# clock.net
KiCad netlist of a schematic drawn in EAGLE
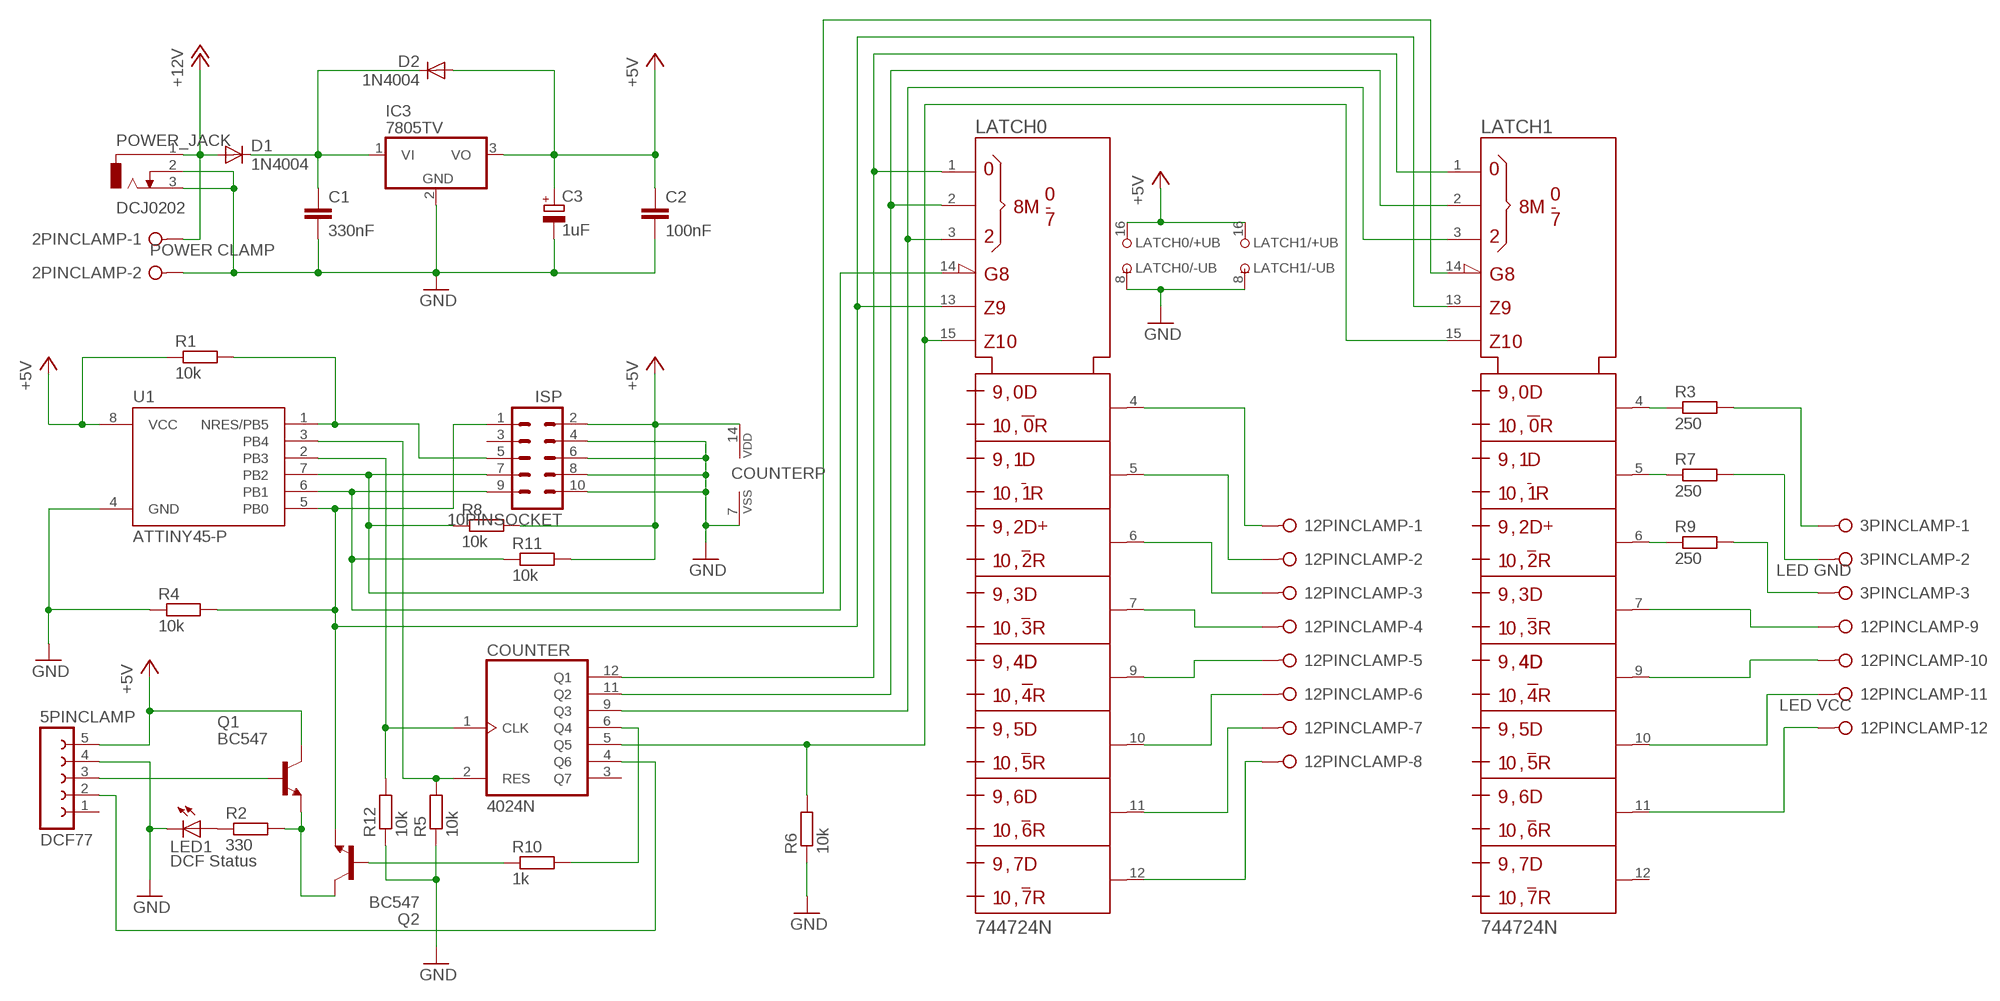
[diagram p0: schematic, sheet 1]

(export (version "E")
  (design (tool "Eeschema 10.0.6"))
  (components
    (comp (ref "2PINCLAMP")
      (value "POWER CLAMP")
      (footprint "eagle-import:W237-132")
      (libsource (lib "eagle-import") (part "W237-02P"))
    )
    (comp (ref "3PINCLAMP")
      (value "LED GND")
      (footprint "eagle-import:W237-3E")
      (libsource (lib "eagle-import") (part "W237-3E"))
    )
    (comp (ref "5PINCLAMP")
      (value "DCF77")
      (footprint "eagle-import:FE05-1")
      (libsource (lib "eagle-import") (part "FE05-1"))
    )
    (comp (ref "10PINSOCKET")
      (value "ISP")
      (footprint "eagle-import:ML10")
      (libsource (lib "eagle-import") (part "ML10"))
    )
    (comp (ref "12PINCLAMP")
      (value "LED VCC")
      (footprint "eagle-import:W237-12P")
      (libsource (lib "eagle-import") (part "W237-12P"))
    )
    (comp (ref "C1")
      (value "330nF")
      (footprint "eagle-import:C050-025X075")
      (libsource (lib "eagle-import") (part "C-EU050-025X075"))
    )
    (comp (ref "C2")
      (value "100nF")
      (footprint "eagle-import:C050-025X075")
      (libsource (lib "eagle-import") (part "C-EU050-025X075"))
    )
    (comp (ref "C3")
      (value "1uF")
      (footprint "eagle-import:E2-4")
      (libsource (lib "eagle-import") (part "CPOL-EUE2-4"))
    )
    (comp (ref "COUNTER")
      (value "4024N")
      (footprint "eagle-import:DIL14")
      (libsource (lib "eagle-import") (part "4024N"))
    )
    (comp (ref "D1")
      (value "1N4004")
      (footprint "eagle-import:DO41-10")
      (libsource (lib "eagle-import") (part "1N4004"))
    )
    (comp (ref "D2")
      (value "1N4004")
      (footprint "eagle-import:DO41-10")
      (libsource (lib "eagle-import") (part "1N4004"))
    )
    (comp (ref "IC3")
      (value "7805TV")
      (footprint "eagle-import:TO220V")
      (libsource (lib "eagle-import") (part "78TV05"))
    )
    (comp (ref "LATCH0")
      (value "744724N")
      (footprint "eagle-import:DIL16")
      (libsource (lib "eagle-import") (part "744724N"))
    )
    (comp (ref "LATCH1")
      (value "744724N")
      (footprint "eagle-import:DIL16")
      (libsource (lib "eagle-import") (part "744724N"))
    )
    (comp (ref "LED1")
      (value "DCF Status")
      (footprint "eagle-import:LED5MM")
      (libsource (lib "eagle-import") (part "LED5MM"))
    )
    (comp (ref "POWER_JACK")
      (value "DCJ0202")
      (footprint "eagle-import:DCJ0202")
      (libsource (lib "eagle-import") (part "DCJ0202"))
    )
    (comp (ref "Q1")
      (value "BC547")
      (footprint "eagle-import:TO92")
      (libsource (lib "eagle-import") (part "BC547"))
    )
    (comp (ref "Q2")
      (value "BC547")
      (footprint "eagle-import:TO92")
      (libsource (lib "eagle-import") (part "BC547"))
    )
    (comp (ref "R1")
      (value "10k")
      (footprint "eagle-import:0204_5")
      (libsource (lib "eagle-import") (part "R-EU_0204/5"))
    )
    (comp (ref "R2")
      (value "330")
      (footprint "eagle-import:0204_5")
      (libsource (lib "eagle-import") (part "R-EU_0204/5"))
    )
    (comp (ref "R3")
      (value "250")
      (footprint "eagle-import:0204_5")
      (libsource (lib "eagle-import") (part "R-EU_0204/5"))
    )
    (comp (ref "R4")
      (value "10k")
      (footprint "eagle-import:0204_5")
      (libsource (lib "eagle-import") (part "R-EU_0204/5"))
    )
    (comp (ref "R5")
      (value "10k")
      (footprint "eagle-import:0204_5")
      (libsource (lib "eagle-import") (part "R-EU_0204/5"))
    )
    (comp (ref "R6")
      (value "10k")
      (footprint "eagle-import:0204_5")
      (libsource (lib "eagle-import") (part "R-EU_0204/5"))
    )
    (comp (ref "R7")
      (value "250")
      (footprint "eagle-import:0204_5")
      (libsource (lib "eagle-import") (part "R-EU_0204/5"))
    )
    (comp (ref "R8")
      (value "10k")
      (footprint "eagle-import:0204_5")
      (libsource (lib "eagle-import") (part "R-EU_0204/5"))
    )
    (comp (ref "R9")
      (value "250")
      (footprint "eagle-import:0204_5")
      (libsource (lib "eagle-import") (part "R-EU_0204/5"))
    )
    (comp (ref "R10")
      (value "1k")
      (footprint "eagle-import:0204_5")
      (libsource (lib "eagle-import") (part "R-EU_0204/5"))
    )
    (comp (ref "R11")
      (value "10k")
      (footprint "eagle-import:0204_5")
      (libsource (lib "eagle-import") (part "R-EU_0204/5"))
    )
    (comp (ref "R12")
      (value "10k")
      (footprint "eagle-import:0204_5")
      (libsource (lib "eagle-import") (part "R-EU_0204/5"))
    )
    (comp (ref "U1")
      (value "ATTINY45-P")
      (footprint "eagle-import:PDIP08_300MIL")
      (libsource (lib "eagle-import") (part "ATTINY45P-"))
    )
  )
  (nets
    (net (code "1") (name "+5V") (class "Default")
      (node (ref "10PINSOCKET") (pin "2") (pinfunction "2_2") (pintype "passive"))
      (node (ref "5PINCLAMP") (pin "5") (pinfunction "5_5") (pintype "passive"))
      (node (ref "C2") (pin "1") (pinfunction "1_1") (pintype "passive"))
      (node (ref "C3") (pin "+") (pinfunction "+_+") (pintype "passive"))
      (node (ref "COUNTER") (pin "14") (pinfunction "VDD_14") (pintype "power_in"))
      (node (ref "D2") (pin "A") (pinfunction "A_A") (pintype "passive"))
      (node (ref "IC3") (pin "3") (pinfunction "VO_3") (pintype "passive"))
      (node (ref "LATCH0") (pin "16") (pinfunction "+UB_16") (pintype "power_in"))
      (node (ref "LATCH1") (pin "16") (pinfunction "+UB_16") (pintype "power_in"))
      (node (ref "Q1") (pin "3") (pinfunction "C_3") (pintype "passive"))
      (node (ref "R1") (pin "1") (pinfunction "1_1") (pintype "passive"))
      (node (ref "R11") (pin "2") (pinfunction "2_2") (pintype "passive"))
      (node (ref "R8") (pin "2") (pinfunction "2_2") (pintype "passive"))
      (node (ref "U1") (pin "8") (pinfunction "VCC_8") (pintype "power_in"))
    )
    (net (code "2") (name "+12V") (class "Default")
      (node (ref "2PINCLAMP") (pin "1") (pinfunction "KL_1") (pintype "passive"))
      (node (ref "D1") (pin "A") (pinfunction "A_A") (pintype "passive"))
      (node (ref "POWER_JACK") (pin "1") (pinfunction "1_1") (pintype "passive"))
    )
    (net (code "3") (name "GND") (class "Default")
      (node (ref "10PINSOCKET") (pin "10") (pinfunction "10_10") (pintype "passive"))
      (node (ref "10PINSOCKET") (pin "4") (pinfunction "4_4") (pintype "passive"))
      (node (ref "10PINSOCKET") (pin "6") (pinfunction "6_6") (pintype "passive"))
      (node (ref "10PINSOCKET") (pin "8") (pinfunction "8_8") (pintype "passive"))
      (node (ref "2PINCLAMP") (pin "2") (pinfunction "KL_2") (pintype "passive"))
      (node (ref "5PINCLAMP") (pin "4") (pinfunction "4_4") (pintype "passive"))
      (node (ref "C1") (pin "2") (pinfunction "2_2") (pintype "passive"))
      (node (ref "C2") (pin "2") (pinfunction "2_2") (pintype "passive"))
      (node (ref "C3") (pin "-") (pinfunction "-_-") (pintype "passive"))
      (node (ref "COUNTER") (pin "7") (pinfunction "VSS_7") (pintype "power_in"))
      (node (ref "IC3") (pin "2") (pinfunction "GND_2") (pintype "passive"))
      (node (ref "LATCH0") (pin "8") (pinfunction "-UB_8") (pintype "power_in"))
      (node (ref "LATCH1") (pin "8") (pinfunction "-UB_8") (pintype "power_in"))
      (node (ref "LED1") (pin "K") (pinfunction "C_K") (pintype "passive"))
      (node (ref "POWER_JACK") (pin "2") (pinfunction "2_2") (pintype "passive"))
      (node (ref "POWER_JACK") (pin "3") (pinfunction "3_3") (pintype "passive"))
      (node (ref "R12") (pin "1") (pinfunction "1_1") (pintype "passive"))
      (node (ref "R4") (pin "1") (pinfunction "1_1") (pintype "passive"))
      (node (ref "R5") (pin "1") (pinfunction "1_1") (pintype "passive"))
      (node (ref "R6") (pin "1") (pinfunction "1_1") (pintype "passive"))
      (node (ref "U1") (pin "4") (pinfunction "GND_4") (pintype "power_in"))
    )
    (net (code "4") (name "Net-(3PINCLAMPA-KL)") (class "Default")
      (node (ref "3PINCLAMP") (pin "1") (pinfunction "KL_1") (pintype "passive"))
      (node (ref "R3") (pin "2") (pinfunction "2_2") (pintype "passive"))
    )
    (net (code "5") (name "Net-(3PINCLAMPB-KL)") (class "Default")
      (node (ref "3PINCLAMP") (pin "2") (pinfunction "KL_2") (pintype "passive"))
      (node (ref "R7") (pin "2") (pinfunction "2_2") (pintype "passive"))
    )
    (net (code "6") (name "Net-(3PINCLAMPC-KL)") (class "Default")
      (node (ref "3PINCLAMP") (pin "3") (pinfunction "KL_3") (pintype "passive"))
      (node (ref "R9") (pin "2") (pinfunction "2_2") (pintype "passive"))
    )
    (net (code "7") (name "Net-(12PINCLAMPA-KL)") (class "Default")
      (node (ref "12PINCLAMP") (pin "1") (pinfunction "KL_1") (pintype "passive"))
      (node (ref "LATCH0") (pin "4") (pinfunction "Q0_4") (pintype "output"))
    )
    (net (code "8") (name "Net-(12PINCLAMPB-KL)") (class "Default")
      (node (ref "12PINCLAMP") (pin "10") (pinfunction "KL_10") (pintype "passive"))
      (node (ref "LATCH1") (pin "9") (pinfunction "Q4_9") (pintype "output"))
    )
    (net (code "9") (name "Net-(12PINCLAMPC-KL)") (class "Default")
      (node (ref "12PINCLAMP") (pin "11") (pinfunction "KL_11") (pintype "passive"))
      (node (ref "LATCH1") (pin "10") (pinfunction "Q5_10") (pintype "output"))
    )
    (net (code "10") (name "Net-(12PINCLAMPD-KL)") (class "Default")
      (node (ref "12PINCLAMP") (pin "12") (pinfunction "KL_12") (pintype "passive"))
      (node (ref "LATCH1") (pin "11") (pinfunction "Q6_11") (pintype "output"))
    )
    (net (code "11") (name "Net-(12PINCLAMPE-KL)") (class "Default")
      (node (ref "12PINCLAMP") (pin "2") (pinfunction "KL_2") (pintype "passive"))
      (node (ref "LATCH0") (pin "5") (pinfunction "Q1_5") (pintype "output"))
    )
    (net (code "12") (name "Net-(12PINCLAMPF-KL)") (class "Default")
      (node (ref "12PINCLAMP") (pin "3") (pinfunction "KL_3") (pintype "passive"))
      (node (ref "LATCH0") (pin "6") (pinfunction "Q2_6") (pintype "output"))
    )
    (net (code "13") (name "Net-(12PINCLAMPG-KL)") (class "Default")
      (node (ref "12PINCLAMP") (pin "4") (pinfunction "KL_4") (pintype "passive"))
      (node (ref "LATCH0") (pin "7") (pinfunction "Q3_7") (pintype "output"))
    )
    (net (code "14") (name "Net-(12PINCLAMPH-KL)") (class "Default")
      (node (ref "12PINCLAMP") (pin "5") (pinfunction "KL_5") (pintype "passive"))
      (node (ref "LATCH0") (pin "9") (pinfunction "Q4_9") (pintype "output"))
    )
    (net (code "15") (name "Net-(12PINCLAMPI-KL)") (class "Default")
      (node (ref "12PINCLAMP") (pin "6") (pinfunction "KL_6") (pintype "passive"))
      (node (ref "LATCH0") (pin "10") (pinfunction "Q5_10") (pintype "output"))
    )
    (net (code "16") (name "Net-(12PINCLAMPJ-KL)") (class "Default")
      (node (ref "12PINCLAMP") (pin "7") (pinfunction "KL_7") (pintype "passive"))
      (node (ref "LATCH0") (pin "11") (pinfunction "Q6_11") (pintype "output"))
    )
    (net (code "17") (name "Net-(12PINCLAMPK-KL)") (class "Default")
      (node (ref "12PINCLAMP") (pin "8") (pinfunction "KL_8") (pintype "passive"))
      (node (ref "LATCH0") (pin "12") (pinfunction "Q7_12") (pintype "output"))
    )
    (net (code "18") (name "Net-(12PINCLAMPL-KL)") (class "Default")
      (node (ref "12PINCLAMP") (pin "9") (pinfunction "KL_9") (pintype "passive"))
      (node (ref "LATCH1") (pin "7") (pinfunction "Q3_7") (pintype "output"))
    )
    (net (code "19") (name "Net-(COUNTERA-CLK)") (class "Default")
      (node (ref "COUNTER") (pin "1") (pinfunction "CLK_1") (pintype "input"))
      (node (ref "R12") (pin "2") (pinfunction "2_2") (pintype "passive"))
      (node (ref "U1") (pin "2") (pinfunction "PB3_2") (pintype "bidirectional"))
    )
    (net (code "20") (name "Net-(COUNTERA-Q1)") (class "Default")
      (node (ref "COUNTER") (pin "12") (pinfunction "Q1_12") (pintype "output"))
      (node (ref "LATCH0") (pin "1") (pinfunction "S0_1") (pintype "input"))
      (node (ref "LATCH1") (pin "1") (pinfunction "S0_1") (pintype "input"))
    )
    (net (code "21") (name "Net-(COUNTERA-Q2)") (class "Default")
      (node (ref "COUNTER") (pin "11") (pinfunction "Q2_11") (pintype "output"))
      (node (ref "LATCH0") (pin "2") (pinfunction "S1_2") (pintype "input"))
      (node (ref "LATCH1") (pin "2") (pinfunction "S1_2") (pintype "input"))
    )
    (net (code "22") (name "Net-(COUNTERA-Q3)") (class "Default")
      (node (ref "COUNTER") (pin "9") (pinfunction "Q3_9") (pintype "output"))
      (node (ref "LATCH0") (pin "3") (pinfunction "S2_3") (pintype "input"))
      (node (ref "LATCH1") (pin "3") (pinfunction "S2_3") (pintype "input"))
    )
    (net (code "23") (name "Net-(COUNTERA-Q4)") (class "Default")
      (node (ref "COUNTER") (pin "6") (pinfunction "Q4_6") (pintype "output"))
      (node (ref "R10") (pin "2") (pinfunction "2_2") (pintype "passive"))
    )
    (net (code "24") (name "Net-(COUNTERA-Q5)") (class "Default")
      (node (ref "COUNTER") (pin "5") (pinfunction "Q5_5") (pintype "output"))
      (node (ref "LATCH0") (pin "15") (pinfunction "CLR_15") (pintype "input"))
      (node (ref "LATCH1") (pin "15") (pinfunction "CLR_15") (pintype "input"))
      (node (ref "R6") (pin "2") (pinfunction "2_2") (pintype "passive"))
    )
    (net (code "25") (name "Net-(COUNTERA-Q6)") (class "Default")
      (node (ref "5PINCLAMP") (pin "2") (pinfunction "2_2") (pintype "passive"))
      (node (ref "COUNTER") (pin "4") (pinfunction "Q6_4") (pintype "output"))
    )
    (net (code "26") (name "Net-(COUNTERA-RES)") (class "Default")
      (node (ref "COUNTER") (pin "2") (pinfunction "RES_2") (pintype "input"))
      (node (ref "R5") (pin "2") (pinfunction "2_2") (pintype "passive"))
      (node (ref "U1") (pin "3") (pinfunction "PB4_3") (pintype "bidirectional"))
    )
    (net (code "27") (name "Net-(IC3-VI)") (class "Default")
      (node (ref "C1") (pin "1") (pinfunction "1_1") (pintype "passive"))
      (node (ref "D1") (pin "C") (pinfunction "C_C") (pintype "passive"))
      (node (ref "D2") (pin "C") (pinfunction "C_C") (pintype "passive"))
      (node (ref "IC3") (pin "1") (pinfunction "VI_1") (pintype "input"))
    )
    (net (code "28") (name "Net-(LATCH0C-D)") (class "Default")
      (node (ref "10PINSOCKET") (pin "1") (pinfunction "1_1") (pintype "passive"))
      (node (ref "LATCH0") (pin "13") (pinfunction "D_13") (pintype "input"))
      (node (ref "LATCH1") (pin "13") (pinfunction "D_13") (pintype "input"))
      (node (ref "Q2") (pin "1") (pinfunction "E_1") (pintype "passive"))
      (node (ref "R4") (pin "2") (pinfunction "2_2") (pintype "passive"))
      (node (ref "U1") (pin "5") (pinfunction "PB0_5") (pintype "bidirectional"))
    )
    (net (code "29") (name "Net-(LATCH0C-~{G})") (class "Default")
      (node (ref "10PINSOCKET") (pin "9") (pinfunction "9_9") (pintype "passive"))
      (node (ref "LATCH0") (pin "14") (pinfunction "~{G}_14") (pintype "input"))
      (node (ref "R11") (pin "1") (pinfunction "1_1") (pintype "passive"))
      (node (ref "U1") (pin "6") (pinfunction "PB1_6") (pintype "bidirectional"))
    )
    (net (code "30") (name "Net-(LATCH1C-Q0)") (class "Default")
      (node (ref "LATCH1") (pin "4") (pinfunction "Q0_4") (pintype "output"))
      (node (ref "R3") (pin "1") (pinfunction "1_1") (pintype "passive"))
    )
    (net (code "31") (name "Net-(LATCH1C-Q1)") (class "Default")
      (node (ref "LATCH1") (pin "5") (pinfunction "Q1_5") (pintype "output"))
      (node (ref "R7") (pin "1") (pinfunction "1_1") (pintype "passive"))
    )
    (net (code "32") (name "Net-(LATCH1C-Q2)") (class "Default")
      (node (ref "LATCH1") (pin "6") (pinfunction "Q2_6") (pintype "output"))
      (node (ref "R9") (pin "1") (pinfunction "1_1") (pintype "passive"))
    )
    (net (code "33") (name "Net-(LATCH1C-~{G})") (class "Default")
      (node (ref "10PINSOCKET") (pin "7") (pinfunction "7_7") (pintype "passive"))
      (node (ref "LATCH1") (pin "14") (pinfunction "~{G}_14") (pintype "input"))
      (node (ref "R8") (pin "1") (pinfunction "1_1") (pintype "passive"))
      (node (ref "U1") (pin "7") (pinfunction "PB2_7") (pintype "bidirectional"))
    )
    (net (code "34") (name "Net-(LED1-PadA)") (class "Default")
      (node (ref "LED1") (pin "A") (pinfunction "A_A") (pintype "passive"))
      (node (ref "R2") (pin "1") (pinfunction "1_1") (pintype "passive"))
    )
    (net (code "35") (name "Net-(Q1-B)") (class "Default")
      (node (ref "5PINCLAMP") (pin "3") (pinfunction "3_3") (pintype "passive"))
      (node (ref "Q1") (pin "2") (pinfunction "B_2") (pintype "passive"))
    )
    (net (code "36") (name "Net-(Q1-E)") (class "Default")
      (node (ref "Q1") (pin "1") (pinfunction "E_1") (pintype "passive"))
      (node (ref "Q2") (pin "3") (pinfunction "C_3") (pintype "passive"))
      (node (ref "R2") (pin "2") (pinfunction "2_2") (pintype "passive"))
    )
    (net (code "37") (name "Net-(Q2-B)") (class "Default")
      (node (ref "Q2") (pin "2") (pinfunction "B_2") (pintype "passive"))
      (node (ref "R10") (pin "1") (pinfunction "1_1") (pintype "passive"))
    )
    (net (code "38") (name "Net-(U1-NRES{slash}PB5)") (class "Default")
      (node (ref "10PINSOCKET") (pin "5") (pinfunction "5_5") (pintype "passive"))
      (node (ref "R1") (pin "2") (pinfunction "2_2") (pintype "passive"))
      (node (ref "U1") (pin "1") (pinfunction "NRES/PB5_1") (pintype "bidirectional"))
    )
    (net (code "39") (name "unconnected-(5PINCLAMP-Pad1)") (class "Default")
      (node (ref "5PINCLAMP") (pin "1") (pinfunction "1_1") (pintype "passive"))
    )
    (net (code "40") (name "unconnected-(10PINSOCKET-Pad3)") (class "Default")
      (node (ref "10PINSOCKET") (pin "3") (pinfunction "3_3") (pintype "passive"))
    )
    (net (code "41") (name "unconnected-(COUNTERA-Q7-Pad3)") (class "Default")
      (node (ref "COUNTER") (pin "3") (pinfunction "Q7_3") (pintype "output"))
    )
    (net (code "42") (name "unconnected-(LATCH1C-Q7-Pad12)") (class "Default")
      (node (ref "LATCH1") (pin "12") (pinfunction "Q7_12") (pintype "output"))
    )
  )
)
